# Sensor.net
KiCad netlist of a schematic drawn in Altium Designer
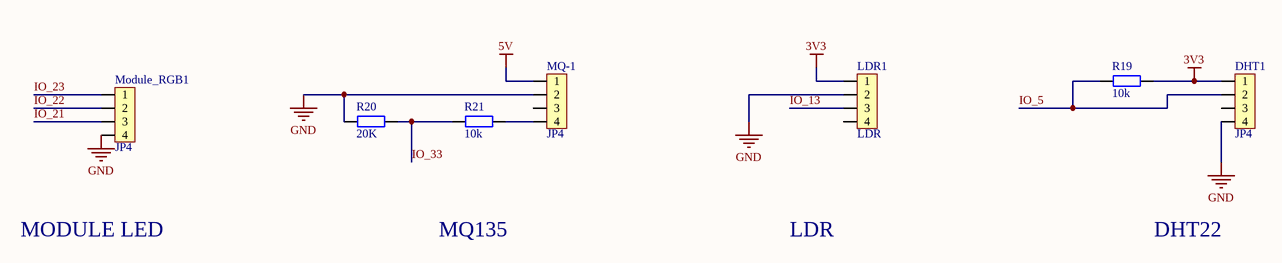
[diagram p0: Sensor.SchDoc]

(export (version "E")
  (design (tool "Eeschema 10.0.6"))
  (components
    (comp (ref "DHT1")
      (value "JP4")
      (footprint "JP4-C1T")
      (description "https://linhkien.cxt.vn/1788-header-duc-3p-xh254-3p-chan-thang-10c.html")
      (fields
        (field (name "MANUFACTURER") "Würth Elektronik eiSos GmbH")
        (field (name "PARTNO") "613004143121")
        (field (name "CREATED BY") "Karrer Zheng")
      )
      (libsource (lib "Main") (part "JP4"))
    )
    (comp (ref "LDR1")
      (value "LDR")
      (footprint "JP4-C1T")
      (description "https://linhkien.cxt.vn/1788-header-duc-3p-xh254-3p-chan-thang-10c.html")
      (fields
        (field (name "MANUFACTURER") "Würth Elektronik eiSos GmbH")
        (field (name "PARTNO") "613004143121")
        (field (name "CREATED BY") "Karrer Zheng")
      )
      (libsource (lib "Main") (part "JP4"))
    )
    (comp (ref "Module_RGB1")
      (value "JP4")
      (footprint "JP4-C1T")
      (fields
        (field (name "MANUFACTURER") "Würth Elektronik eiSos GmbH")
        (field (name "PARTNO") "613004143121")
        (field (name "CREATED BY") "Karrer Zheng")
      )
      (libsource (lib "Main") (part "JP4"))
    )
    (comp (ref "MQ-1")
      (value "JP4")
      (footprint "JP4-C1T")
      (description "https://linhkien.cxt.vn/1788-header-duc-3p-xh254-3p-chan-thang-10c.html")
      (fields
        (field (name "MANUFACTURER") "Würth Elektronik eiSos GmbH")
        (field (name "PARTNO") "613004143121")
        (field (name "CREATED BY") "Karrer Zheng")
      )
      (libsource (lib "Main") (part "JP4"))
    )
    (comp (ref "R19")
      (value "10k")
      (footprint "RES-SMD-0805")
      (description "1k")
      (fields
        (field (name "MANUFACTURER") "Generic Components")
        (field (name "PUBLISHER") "Altium Hobart Technology Centre")
      )
      (libsource (lib "Main") (part "Resistor - SMD"))
    )
    (comp (ref "R20")
      (value "20K")
      (footprint "RES-SMD-0805")
      (fields
        (field (name "MANUFACTURER") "Generic Components")
        (field (name "PUBLISHER") "Altium Hobart Technology Centre")
      )
      (libsource (lib "Main") (part "Resistor - SMD"))
    )
    (comp (ref "R21")
      (value "10k")
      (footprint "RES-SMD-0805")
      (fields
        (field (name "MANUFACTURER") "Generic Components")
        (field (name "PUBLISHER") "Altium Hobart Technology Centre")
      )
      (libsource (lib "Main") (part "Resistor - SMD"))
    )
  )
  (nets
    (net (code "1") (name "/IO_5") (class "Default")
      (node (ref "DHT1") (pin "2") (pinfunction "2_2") (pintype "passive"))
      (node (ref "R19") (pin "2") (pinfunction "2_2") (pintype "passive"))
    )
    (net (code "2") (name "/IO_13") (class "Default")
      (node (ref "LDR1") (pin "3") (pinfunction "3_3") (pintype "passive"))
    )
    (net (code "3") (name "/IO_21") (class "Default")
      (node (ref "Module_RGB1") (pin "3") (pinfunction "3_3") (pintype "passive"))
    )
    (net (code "4") (name "/IO_22") (class "Default")
      (node (ref "Module_RGB1") (pin "2") (pinfunction "2_2") (pintype "passive"))
    )
    (net (code "5") (name "/IO_23") (class "Default")
      (node (ref "Module_RGB1") (pin "1") (pinfunction "1_1") (pintype "passive"))
    )
    (net (code "6") (name "/IO_33") (class "Default")
      (node (ref "R20") (pin "2") (pinfunction "2_2") (pintype "passive"))
      (node (ref "R21") (pin "1") (pinfunction "1_1") (pintype "passive"))
    )
    (net (code "7") (name "3V3") (class "Default")
      (node (ref "DHT1") (pin "1") (pinfunction "1_1") (pintype "passive"))
      (node (ref "LDR1") (pin "1") (pinfunction "1_1") (pintype "passive"))
      (node (ref "R19") (pin "1") (pinfunction "1_1") (pintype "passive"))
    )
    (net (code "8") (name "5V") (class "Default")
      (node (ref "MQ-1") (pin "1") (pinfunction "1_1") (pintype "passive"))
    )
    (net (code "9") (name "GND") (class "Default")
      (node (ref "DHT1") (pin "4") (pinfunction "4_4") (pintype "passive"))
      (node (ref "LDR1") (pin "2") (pinfunction "2_2") (pintype "passive"))
      (node (ref "MQ-1") (pin "2") (pinfunction "2_2") (pintype "passive"))
      (node (ref "Module_RGB1") (pin "4") (pinfunction "4_4") (pintype "passive"))
      (node (ref "R20") (pin "1") (pinfunction "1_1") (pintype "passive"))
    )
    (net (code "10") (name "Net-(MQ-1-Pad4)") (class "Default")
      (node (ref "MQ-1") (pin "4") (pinfunction "4_4") (pintype "passive"))
      (node (ref "R21") (pin "2") (pinfunction "2_2") (pintype "passive"))
    )
    (net (code "11") (name "unconnected-(DHT1-Pad3)") (class "Default")
      (node (ref "DHT1") (pin "3") (pinfunction "3_3") (pintype "passive"))
    )
    (net (code "12") (name "unconnected-(LDR1-Pad4)") (class "Default")
      (node (ref "LDR1") (pin "4") (pinfunction "4_4") (pintype "passive"))
    )
    (net (code "13") (name "unconnected-(MQ-1-Pad3)") (class "Default")
      (node (ref "MQ-1") (pin "3") (pinfunction "3_3") (pintype "passive"))
    )
  )
)
